# v0_1.net
KiCad netlist of a schematic drawn in EAGLE
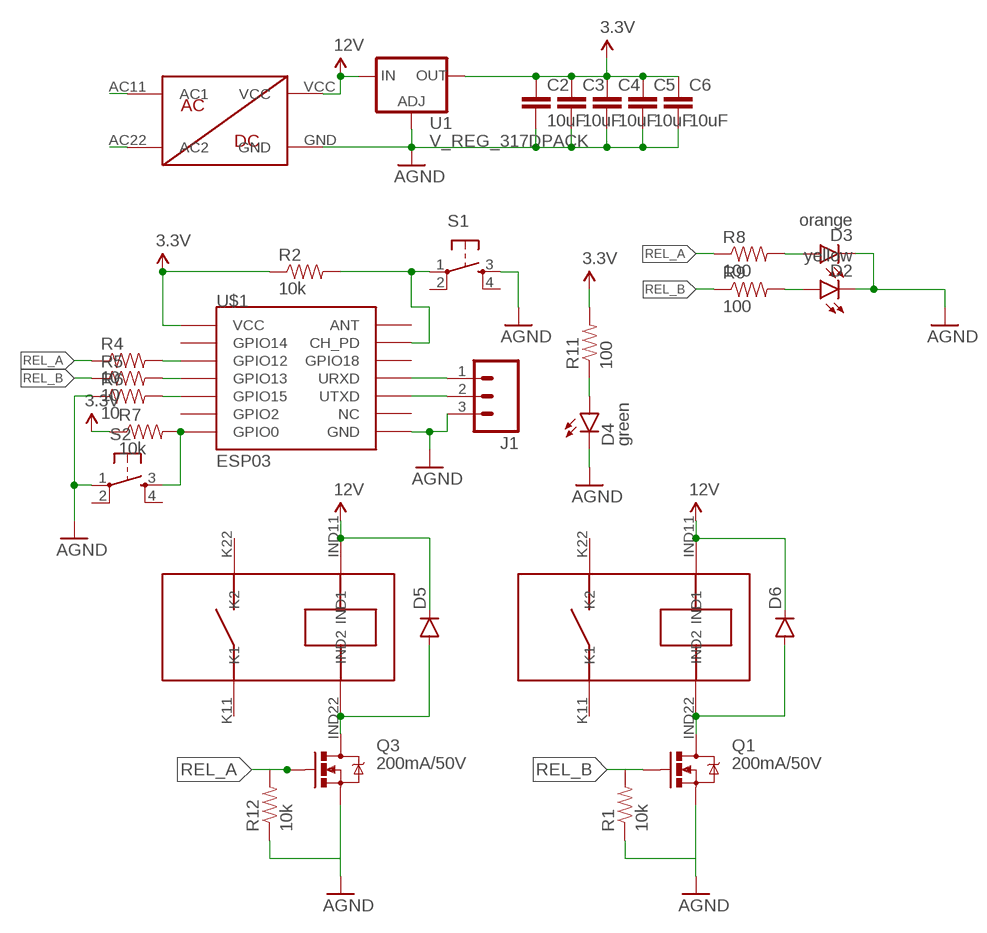
[diagram p0: schematic, sheet 1]

(export (version "E")
  (design (tool "Eeschema 10.0.6"))
  (components
    (comp (ref "C2")
      (value "10uF")
      (footprint "eagle-import:0603-CAP")
      (libsource (lib "eagle-import") (part "10UF-6.3V-20%(0603)"))
    )
    (comp (ref "C3")
      (value "10uF")
      (footprint "eagle-import:0603-CAP")
      (libsource (lib "eagle-import") (part "10UF-6.3V-20%(0603)"))
    )
    (comp (ref "C4")
      (value "10uF")
      (footprint "eagle-import:0603-CAP")
      (libsource (lib "eagle-import") (part "10UF-6.3V-20%(0603)"))
    )
    (comp (ref "C5")
      (value "10uF")
      (footprint "eagle-import:0603-CAP")
      (libsource (lib "eagle-import") (part "10UF-6.3V-20%(0603)"))
    )
    (comp (ref "C6")
      (value "10uF")
      (footprint "eagle-import:0603-CAP")
      (libsource (lib "eagle-import") (part "10UF-6.3V-20%(0603)"))
    )
    (comp (ref "D2")
      (value "yellow")
      (footprint "eagle-import:LED-0603")
      (libsource (lib "eagle-import") (part "LED0603"))
    )
    (comp (ref "D3")
      (value "orange")
      (footprint "eagle-import:LED-0603")
      (libsource (lib "eagle-import") (part "LED0603"))
    )
    (comp (ref "D4")
      (value "green")
      (footprint "eagle-import:LED-0603")
      (libsource (lib "eagle-import") (part "LED0603"))
    )
    (comp (ref "D5")
      (value "DIODESOD123")
      (footprint "eagle-import:SOD-123")
      (libsource (lib "eagle-import") (part "DIODESOD123"))
    )
    (comp (ref "D6")
      (value "DIODESOD123")
      (footprint "eagle-import:SOD-123")
      (libsource (lib "eagle-import") (part "DIODESOD123"))
    )
    (comp (ref "J1")
      (value "M03LONGPADS")
      (footprint "eagle-import:1X03_LONGPADS")
      (libsource (lib "eagle-import") (part "M03LONGPADS"))
    )
    (comp (ref "Q1")
      (value "200mA/50V")
      (footprint "eagle-import:SOT23-3")
      (libsource (lib "eagle-import") (part "MOSFET-NCHANNELBSS138"))
    )
    (comp (ref "Q3")
      (value "200mA/50V")
      (footprint "eagle-import:SOT23-3")
      (libsource (lib "eagle-import") (part "MOSFET-NCHANNELBSS138"))
    )
    (comp (ref "R1")
      (value "10k")
      (footprint "eagle-import:0805")
      (libsource (lib "eagle-import") (part "RESISTOR0805-RES"))
    )
    (comp (ref "R2")
      (value "10k")
      (footprint "eagle-import:0805")
      (libsource (lib "eagle-import") (part "RESISTOR0805-RES"))
    )
    (comp (ref "R4")
      (value "10")
      (footprint "eagle-import:0805")
      (libsource (lib "eagle-import") (part "RESISTOR0805-RES"))
    )
    (comp (ref "R5")
      (value "10")
      (footprint "eagle-import:0805")
      (libsource (lib "eagle-import") (part "RESISTOR0805-RES"))
    )
    (comp (ref "R6")
      (value "10")
      (footprint "eagle-import:0805")
      (libsource (lib "eagle-import") (part "RESISTOR0805-RES"))
    )
    (comp (ref "R7")
      (value "10k")
      (footprint "eagle-import:0805")
      (libsource (lib "eagle-import") (part "RESISTOR0805-RES"))
    )
    (comp (ref "R8")
      (value "100")
      (footprint "eagle-import:0805")
      (libsource (lib "eagle-import") (part "RESISTOR0805-RES"))
    )
    (comp (ref "R9")
      (value "100")
      (footprint "eagle-import:0805")
      (libsource (lib "eagle-import") (part "RESISTOR0805-RES"))
    )
    (comp (ref "R11")
      (value "100")
      (footprint "eagle-import:0805")
      (libsource (lib "eagle-import") (part "RESISTOR0805-RES"))
    )
    (comp (ref "R12")
      (value "10k")
      (footprint "eagle-import:0805")
      (libsource (lib "eagle-import") (part "RESISTOR0805-RES"))
    )
    (comp (ref "S1")
      (value "TAC_SWITCHPTH")
      (footprint "eagle-import:TACTILE-PTH")
      (libsource (lib "eagle-import") (part "TAC_SWITCHPTH"))
    )
    (comp (ref "S2")
      (value "TAC_SWITCHPTH")
      (footprint "eagle-import:TACTILE-PTH")
      (libsource (lib "eagle-import") (part "TAC_SWITCHPTH"))
    )
    (comp (ref "U$1")
      (value "ESP03")
      (footprint "eagle-import:ESP03")
      (libsource (lib "eagle-import") (part "ESP03"))
    )
    (comp (ref "U$8")
      (value "ACDC12V350MA")
      (footprint "eagle-import:ACDC12V350MA")
      (libsource (lib "eagle-import") (part "ACDC12V350MA"))
    )
    (comp (ref "U$9")
      (value "302WP")
      (footprint "eagle-import:302WP")
      (libsource (lib "eagle-import") (part "302WP"))
    )
    (comp (ref "U$10")
      (value "302WP")
      (footprint "eagle-import:302WP")
      (libsource (lib "eagle-import") (part "302WP"))
    )
    (comp (ref "U1")
      (value "V_REG_317DPACK")
      (footprint "eagle-import:V-REG_DPACK")
      (libsource (lib "eagle-import") (part "V_REG_317DPACK"))
    )
  )
  (nets
    (net (code "1") (name "3.3V") (class "Default")
      (node (ref "C2") (pin "1") (pinfunction "1_1") (pintype "passive"))
      (node (ref "C3") (pin "1") (pinfunction "1_1") (pintype "passive"))
      (node (ref "C4") (pin "1") (pinfunction "1_1") (pintype "passive"))
      (node (ref "C5") (pin "1") (pinfunction "1_1") (pintype "passive"))
      (node (ref "C6") (pin "1") (pinfunction "1_1") (pintype "passive"))
      (node (ref "R11") (pin "2") (pinfunction "2_2") (pintype "passive"))
      (node (ref "R2") (pin "1") (pinfunction "1_1") (pintype "passive"))
      (node (ref "R7") (pin "1") (pinfunction "1_1") (pintype "passive"))
      (node (ref "U$1") (pin "VCC") (pinfunction "VCC_VCC") (pintype "bidirectional"))
      (node (ref "U1") (pin "4") (pinfunction "OUT_4") (pintype "output"))
    )
    (net (code "2") (name "12V") (class "Default")
      (node (ref "D5") (pin "C") (pinfunction "C_C") (pintype "passive"))
      (node (ref "D6") (pin "C") (pinfunction "C_C") (pintype "passive"))
      (node (ref "U$10") (pin "IND11") (pinfunction "IND1_IND11") (pintype "bidirectional"))
      (node (ref "U$8") (pin "VCC") (pinfunction "VCC_VCC") (pintype "bidirectional"))
      (node (ref "U$9") (pin "IND11") (pinfunction "IND1_IND11") (pintype "bidirectional"))
      (node (ref "U1") (pin "3") (pinfunction "IN_3") (pintype "input"))
    )
    (net (code "3") (name "AGND") (class "Default")
      (node (ref "C2") (pin "2") (pinfunction "2_2") (pintype "passive"))
      (node (ref "C3") (pin "2") (pinfunction "2_2") (pintype "passive"))
      (node (ref "C4") (pin "2") (pinfunction "2_2") (pintype "passive"))
      (node (ref "C5") (pin "2") (pinfunction "2_2") (pintype "passive"))
      (node (ref "C6") (pin "2") (pinfunction "2_2") (pintype "passive"))
      (node (ref "D2") (pin "C") (pinfunction "C_C") (pintype "passive"))
      (node (ref "D3") (pin "C") (pinfunction "C_C") (pintype "passive"))
      (node (ref "D4") (pin "C") (pinfunction "C_C") (pintype "passive"))
      (node (ref "J1") (pin "3") (pinfunction "3_3") (pintype "passive"))
      (node (ref "Q1") (pin "2") (pinfunction "S_2") (pintype "passive"))
      (node (ref "Q3") (pin "2") (pinfunction "S_2") (pintype "passive"))
      (node (ref "R1") (pin "1") (pinfunction "1_1") (pintype "passive"))
      (node (ref "R12") (pin "1") (pinfunction "1_1") (pintype "passive"))
      (node (ref "R6") (pin "1") (pinfunction "1_1") (pintype "passive"))
      (node (ref "S1") (pin "3") (pinfunction "3_3") (pintype "passive"))
      (node (ref "S2") (pin "1") (pinfunction "1_1") (pintype "passive"))
      (node (ref "U$1") (pin "GND") (pinfunction "GND_GND") (pintype "bidirectional"))
      (node (ref "U$8") (pin "GND") (pinfunction "GND_GND") (pintype "bidirectional"))
      (node (ref "U1") (pin "1") (pinfunction "ADJ_1") (pintype "input"))
    )
    (net (code "4") (name "Net-(D2-PadA)") (class "Default")
      (node (ref "D2") (pin "A") (pinfunction "A_A") (pintype "passive"))
      (node (ref "R9") (pin "2") (pinfunction "2_2") (pintype "passive"))
    )
    (net (code "5") (name "Net-(D3-PadA)") (class "Default")
      (node (ref "D3") (pin "A") (pinfunction "A_A") (pintype "passive"))
      (node (ref "R8") (pin "2") (pinfunction "2_2") (pintype "passive"))
    )
    (net (code "6") (name "Net-(D4-PadA)") (class "Default")
      (node (ref "D4") (pin "A") (pinfunction "A_A") (pintype "passive"))
      (node (ref "R11") (pin "1") (pinfunction "1_1") (pintype "passive"))
    )
    (net (code "7") (name "Net-(J1-Pad1)") (class "Default")
      (node (ref "J1") (pin "1") (pinfunction "1_1") (pintype "passive"))
      (node (ref "U$1") (pin "URXD") (pinfunction "URXD_URXD") (pintype "bidirectional"))
    )
    (net (code "8") (name "Net-(J1-Pad2)") (class "Default")
      (node (ref "J1") (pin "2") (pinfunction "2_2") (pintype "passive"))
      (node (ref "U$1") (pin "UTXD") (pinfunction "UTXD_UTXD") (pintype "bidirectional"))
    )
    (net (code "9") (name "Net-(Q1-D)") (class "Default")
      (node (ref "D6") (pin "A") (pinfunction "A_A") (pintype "passive"))
      (node (ref "Q1") (pin "3") (pinfunction "D_3") (pintype "passive"))
      (node (ref "U$9") (pin "IND22") (pinfunction "IND2_IND22") (pintype "bidirectional"))
    )
    (net (code "10") (name "Net-(Q3-D)") (class "Default")
      (node (ref "D5") (pin "A") (pinfunction "A_A") (pintype "passive"))
      (node (ref "Q3") (pin "3") (pinfunction "D_3") (pintype "passive"))
      (node (ref "U$10") (pin "IND22") (pinfunction "IND2_IND22") (pintype "bidirectional"))
    )
    (net (code "11") (name "Net-(R2-Pad2)") (class "Default")
      (node (ref "R2") (pin "2") (pinfunction "2_2") (pintype "passive"))
      (node (ref "S1") (pin "1") (pinfunction "1_1") (pintype "passive"))
      (node (ref "U$1") (pin "CH_PD") (pinfunction "CH_PD_CH_PD") (pintype "bidirectional"))
    )
    (net (code "12") (name "Net-(R4-Pad2)") (class "Default")
      (node (ref "R4") (pin "2") (pinfunction "2_2") (pintype "passive"))
      (node (ref "U$1") (pin "GPIO12") (pinfunction "GPIO12_GPIO12") (pintype "bidirectional"))
    )
    (net (code "13") (name "Net-(R5-Pad2)") (class "Default")
      (node (ref "R5") (pin "2") (pinfunction "2_2") (pintype "passive"))
      (node (ref "U$1") (pin "GPIO13") (pinfunction "GPIO13_GPIO13") (pintype "bidirectional"))
    )
    (net (code "14") (name "Net-(R6-Pad2)") (class "Default")
      (node (ref "R6") (pin "2") (pinfunction "2_2") (pintype "passive"))
      (node (ref "U$1") (pin "GPIO15") (pinfunction "GPIO15_GPIO15") (pintype "bidirectional"))
    )
    (net (code "15") (name "Net-(R7-Pad2)") (class "Default")
      (node (ref "R7") (pin "2") (pinfunction "2_2") (pintype "passive"))
      (node (ref "S2") (pin "3") (pinfunction "3_3") (pintype "passive"))
      (node (ref "U$1") (pin "GPIO0") (pinfunction "GPIO0_GPIO0") (pintype "bidirectional"))
    )
    (net (code "16") (name "REL_A") (class "Default")
      (node (ref "Q3") (pin "1") (pinfunction "G_1") (pintype "passive"))
      (node (ref "R12") (pin "2") (pinfunction "2_2") (pintype "passive"))
      (node (ref "R4") (pin "1") (pinfunction "1_1") (pintype "passive"))
      (node (ref "R8") (pin "1") (pinfunction "1_1") (pintype "passive"))
    )
    (net (code "17") (name "REL_B") (class "Default")
      (node (ref "Q1") (pin "1") (pinfunction "G_1") (pintype "passive"))
      (node (ref "R1") (pin "2") (pinfunction "2_2") (pintype "passive"))
      (node (ref "R5") (pin "1") (pinfunction "1_1") (pintype "passive"))
      (node (ref "R9") (pin "1") (pinfunction "1_1") (pintype "passive"))
    )
    (net (code "18") (name "unconnected-(S1-Pad2)") (class "Default")
      (node (ref "S1") (pin "2") (pinfunction "2_2") (pintype "passive"))
    )
    (net (code "19") (name "unconnected-(S1-Pad4)") (class "Default")
      (node (ref "S1") (pin "4") (pinfunction "4_4") (pintype "passive"))
    )
    (net (code "20") (name "unconnected-(S2-Pad2)") (class "Default")
      (node (ref "S2") (pin "2") (pinfunction "2_2") (pintype "passive"))
    )
    (net (code "21") (name "unconnected-(S2-Pad4)") (class "Default")
      (node (ref "S2") (pin "4") (pinfunction "4_4") (pintype "passive"))
    )
    (net (code "22") (name "unconnected-(U$1-PadANT)") (class "Default")
      (node (ref "U$1") (pin "ANT") (pinfunction "ANT_ANT") (pintype "bidirectional"))
    )
    (net (code "23") (name "unconnected-(U$1-PadGPIO2)") (class "Default")
      (node (ref "U$1") (pin "GPIO2") (pinfunction "GPIO2_GPIO2") (pintype "bidirectional"))
    )
    (net (code "24") (name "unconnected-(U$1-PadGPIO14)") (class "Default")
      (node (ref "U$1") (pin "GPIO14") (pinfunction "GPIO14_GPIO14") (pintype "bidirectional"))
    )
    (net (code "25") (name "unconnected-(U$1-PadGPIO18)") (class "Default")
      (node (ref "U$1") (pin "GPIO18") (pinfunction "GPIO18_GPIO18") (pintype "bidirectional"))
    )
    (net (code "26") (name "unconnected-(U$1-PadNC)") (class "Default")
      (node (ref "U$1") (pin "NC") (pinfunction "NC_NC") (pintype "bidirectional"))
    )
    (net (code "27") (name "unconnected-(U$8-AC1-PadAC11)") (class "Default")
      (node (ref "U$8") (pin "AC11") (pinfunction "AC1_AC11") (pintype "bidirectional"))
    )
    (net (code "28") (name "unconnected-(U$8-AC2-PadAC22)") (class "Default")
      (node (ref "U$8") (pin "AC22") (pinfunction "AC2_AC22") (pintype "bidirectional"))
    )
    (net (code "29") (name "unconnected-(U$9-K1-PadK11)") (class "Default")
      (node (ref "U$9") (pin "K11") (pinfunction "K1_K11") (pintype "bidirectional"))
    )
    (net (code "30") (name "unconnected-(U$9-K2-PadK22)") (class "Default")
      (node (ref "U$9") (pin "K22") (pinfunction "K2_K22") (pintype "bidirectional"))
    )
    (net (code "31") (name "unconnected-(U$10-K1-PadK11)") (class "Default")
      (node (ref "U$10") (pin "K11") (pinfunction "K1_K11") (pintype "bidirectional"))
    )
    (net (code "32") (name "unconnected-(U$10-K2-PadK22)") (class "Default")
      (node (ref "U$10") (pin "K22") (pinfunction "K2_K22") (pintype "bidirectional"))
    )
  )
)
